# air_quality_monitor.net
KiCad netlist of a schematic drawn in Altium Designer
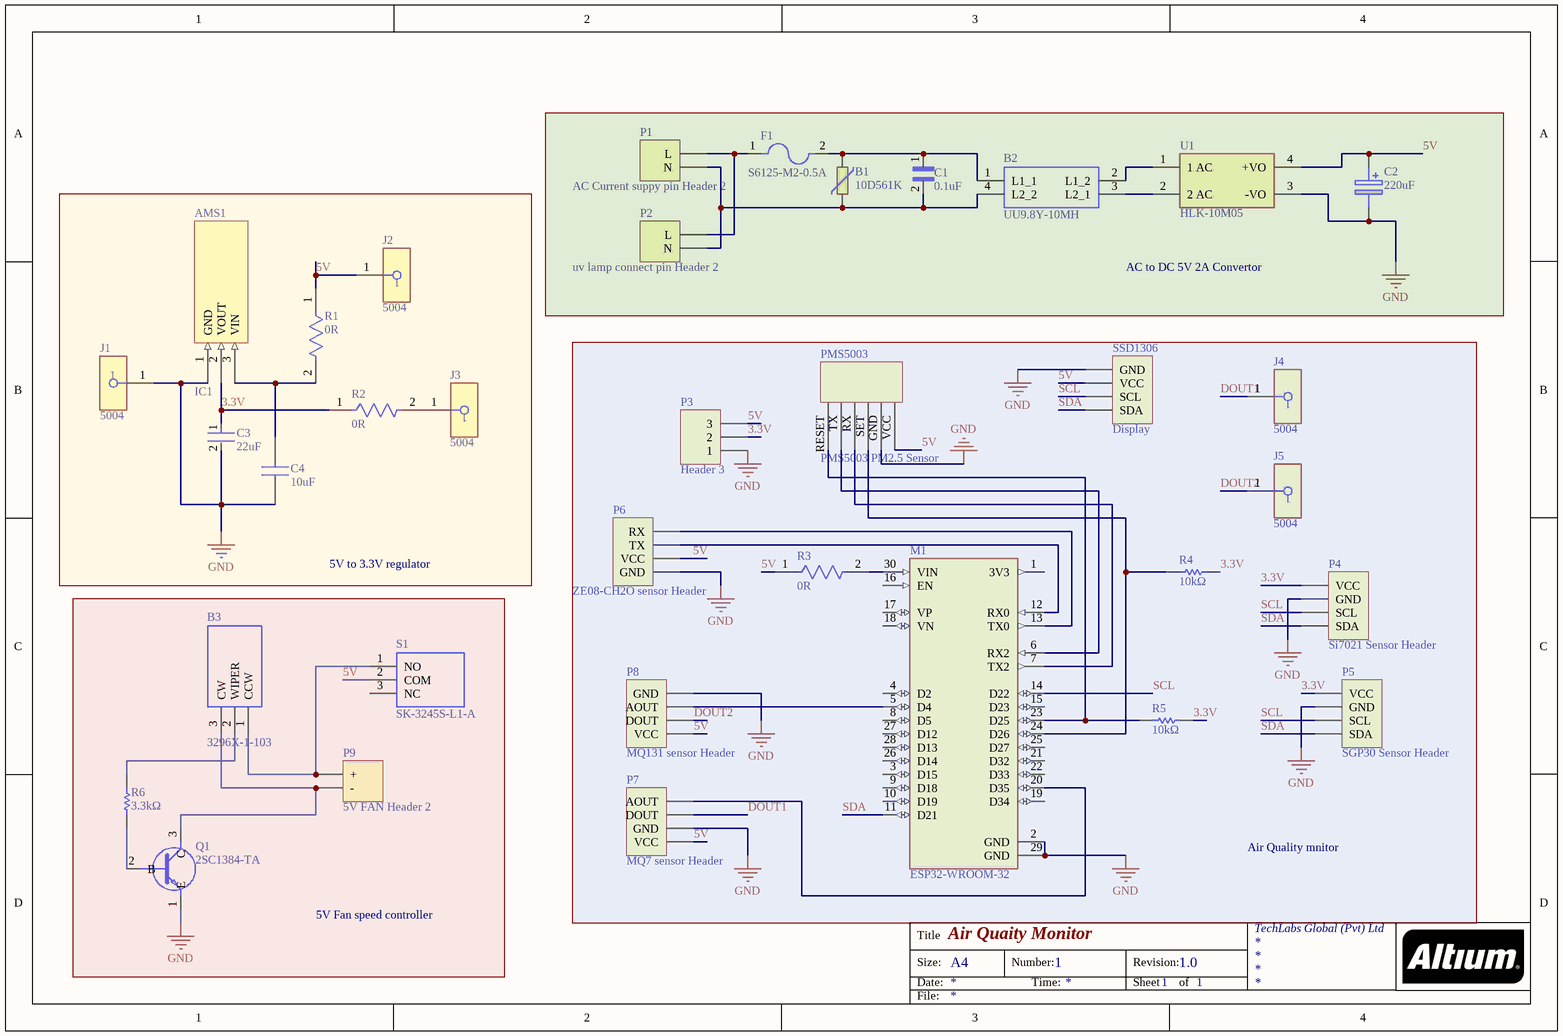
[diagram p0: air quality monitor.SchDoc]

(export (version "E")
  (design (tool "Eeschema 10.0.6"))
  (components
    (comp (ref "AMS1")
      (value "IC1")
      (footprint "SOT89-150P350X150-3N")
      (fields
        (field (name "MANUFACTURER") "YONGYUTAI")
        (field (name "MFR. PART #") "AMS1117-3.3")
        (field (name "LCSC PART #") "C2904742")
      )
      (libsource (lib "AMS1117-3.3") (part "IC?"))
    )
    (comp (ref "B1")
      (value "10D561K")
      (footprint "10D561K")
      (description "920V 42.3J 180pF@1kHz 460V 350V 504V~616V 2.5kA Plugin Varistors ROHS")
      (fields (field (name "LCSC PART #") "C113236") (field (name "MANUFACTURER") "Hongzhi Elec"))
      (libsource (lib "10D561K") (part "10D561K"))
    )
    (comp (ref "B2")
      (value "UU9.8Y-10MH")
      (footprint "UU98Y10MH")
      (description "10mH@1kHz 1.2Ω 2 500mA 50V Plugin Common Mode Filters ROHS")
      (fields
        (field (name "MANUFACTURER") "FH (Guangdong Fenghua Advanced Tech)")
        (field (name "LCSC PART#") "C75192")
      )
      (libsource (lib "UU9.8Y-10MH") (part "UU9.8Y-10MH"))
    )
    (comp (ref "B3")
      (value "3296X-1-103")
      (footprint "3296X1223LF")
      (description "±10% 10kΩ Plugin Variable Resistors/Potentiometers ROHS")
      (fields
        (field (name "MANUFACTURER") " BOCHEN(Chengdu Guosheng Tech)")
        (field (name "LCSC PART #") "C118955")
      )
      (libsource (lib "3296X-1-103") (part "3296X-1-103"))
    )
    (comp (ref "C1")
      (value "0.1uF")
      (footprint "MPX-104K275VAC-C-D2")
      (description "0.1uF ±10% -40℃~+110℃ X2 275VAC Radial Leaded,P=15mm Suppression Capacitors ROHS")
      (fields (field (name "LCSC PART #") "C3249976") (field (name "MANUFACTURER") "CORETONG"))
      (libsource (lib "MPX-104K275VAC-C-D2") (part "MPX-104K275VAC-C-D2"))
    )
    (comp (ref "C2")
      (value "220uF")
      (footprint "CAPAE830X1050N")
      (fields
        (field (name "MANUFACTURER") "Nichicon")
        (field (name "MFR.PART #") "UUR1C221MNL1GS")
        (field (name "LCSC PART#") "C445237")
      )
      (libsource (lib "UUR1C221MNL1GS") (part "UUR1C221MNL1GS"))
    )
    (comp (ref "C3")
      (value "22uF")
      (footprint "FP-GRM219-0_2-0_15-IPC_A")
      (description "Chip Multilayer Ceramic Capacitors for General Purpose, 0805, 22uF, X5R, 15%, 20%, 16V")
      (fields (field (name "MFR. PART #") "GRM219R61C226ME15L") (field (name "LCSC PART #") "C162295"))
      (libsource (lib "Altium Content Vault") (part "b4654b650e69147ec39a6b967a45e02"))
    )
    (comp (ref "C4")
      (value "10uF")
      (footprint "CAPC1005X70N")
      (description "6.3V 10uF X5R ±20% 0402 Multilayer Ceramic Capacitors MLCC - SMD/SMT ROHS")
      (fields
        (field (name "MANUFACTURER") "Samsung Electro-Mechanics")
        (field (name "MFR. PART #") "CL05A106MQ5NUNC")
      )
      (libsource (lib "CL05A106MQ5NUNC") (part "CL05A106MQ5NUNC"))
    )
    (comp (ref "F1")
      (value "S6125-M2-0.5A")
      (footprint "CAPC6125X25N")
      (description "SMD Fuses ROHS")
      (fields (field (name "LCSC PART #") "C845172") (field (name "MANUFACTURER") "SART(Nanjing Sart Tech)"))
      (libsource (lib "S6125-M2-0.5A") (part "S6125-M2-0.5A"))
    )
    (comp (ref "J1")
      (value "5004")
      (footprint "FP-5004-MFG")
      (description "PC TEST POINT MINIATURE YELLOW")
      (fields (field (name "MANUFACTURER") "Keystone") (field (name "LCSC PART #") "C2906762"))
      (libsource (lib "Altium Content Vault") (part "98815daf2f2c152b0c43f5ab9800df6"))
    )
    (comp (ref "J2")
      (value "5004")
      (footprint "FP-5004-MFG")
      (description "PC TEST POINT MINIATURE YELLOW")
      (fields (field (name "MANUFACTURER") "Keystone") (field (name "LCSC PART #") "C2906762"))
      (libsource (lib "") (part "98815daf2f2c152b0c43f5ab9800df6_1"))
    )
    (comp (ref "J3")
      (value "5004")
      (footprint "FP-5004-MFG")
      (description "PC TEST POINT MINIATURE YELLOW")
      (fields (field (name "MANUFACTURER") "Keystone") (field (name "LCSC PART #") "C2906762"))
      (libsource (lib "") (part "98815daf2f2c152b0c43f5ab9800df6_1"))
    )
    (comp (ref "J4")
      (value "5004")
      (footprint "FP-5004-MFG")
      (description "PC TEST POINT MINIATURE YELLOW")
      (fields (field (name "MANUFACTURER") "Keystone") (field (name "LCSC PART #") "C2906762"))
      (libsource (lib "") (part "98815daf2f2c152b0c43f5ab9800df6_1"))
    )
    (comp (ref "J5")
      (value "5004")
      (footprint "FP-5004-MFG")
      (description "PC TEST POINT MINIATURE YELLOW")
      (fields (field (name "MANUFACTURER") "Keystone") (field (name "LCSC PART #") "C2906762"))
      (libsource (lib "") (part "98815daf2f2c152b0c43f5ab9800df6_1"))
    )
    (comp (ref "M1")
      (value "ESP32-WROOM-32")
      (footprint "ESP32-DEVKIT-V1")
      (libsource (lib "Modules") (part "ESP32-DEVKIT-V1"))
    )
    (comp (ref "P1")
      (value "AC Current suppy pin Header 2")
      (footprint "HDR1X2")
      (description "Header, 2-Pin")
      (fields (field (name "PUBLISHER") "Altium Limited"))
      (libsource (lib "Miscellaneous Connectors") (part "Header 2"))
    )
    (comp (ref "P2")
      (value "uv lamp connect pin Header 2")
      (footprint "HDR1X2")
      (description "Header, 2-Pin")
      (fields (field (name "PUBLISHER") "Altium Limited"))
      (libsource (lib "Miscellaneous Connectors") (part "Header 2"))
    )
    (comp (ref "P3")
      (value "Header 3")
      (footprint "HDR1X3")
      (description "Header, 3-Pin")
      (fields (field (name "PUBLISHER") "Altium Limited"))
      (libsource (lib "Miscellaneous Connectors") (part "Header 3"))
    )
    (comp (ref "P4")
      (value "Si7021 Sensor Header")
      (footprint "HDR1X4")
      (description "Header, 4-Pin")
      (libsource (lib "Miscellaneous Connectors") (part "Header 4"))
    )
    (comp (ref "P5")
      (value "SGP30 Sensor Header")
      (footprint "HDR1X4")
      (description "Header, 4-Pin")
      (fields (field (name "PUBLISHER") "Altium Limited"))
      (libsource (lib "Miscellaneous Connectors") (part "Header 4"))
    )
    (comp (ref "P6")
      (value "ZE08-CH2O sensor Header")
      (footprint "HDR1X4")
      (description "- Sensor Modules ROHS")
      (fields
        (field (name "MFR.PART #") "ZE08-CH2O")
        (field (name "MANUFACTURER") "Zhengzhou Winsen Elec Tech")
      )
      (libsource (lib "") (part "Header 4_2"))
    )
    (comp (ref "P7")
      (value "MQ7 sensor Header")
      (footprint "HDR1X4")
      (description "Header, 4-Pin")
      (fields (field (name "PUBLISHER") "Altium Limited"))
      (libsource (lib "") (part "Header 4_1"))
    )
    (comp (ref "P8")
      (value "MQ131 sensor Header")
      (footprint "HDR1X4")
      (description "Header, 4-Pin")
      (fields (field (name "PUBLISHER") "Altium Limited"))
      (libsource (lib "") (part "Header 4_4"))
    )
    (comp (ref "P9")
      (value "5V FAN Header 2")
      (footprint "HDR1X2")
      (description "Header, 2-Pin")
      (fields (field (name "PUBLISHER") "Altium Limited"))
      (libsource (lib "") (part "Header 2_1"))
    )
    (comp (ref "PMS5003")
      (value "PMS5003 PM2.5 Sensor")
      (footprint "PMS5003 PM2.5 Sensor")
      (description "PMS5003 Sensor Modules ROHS")
      (fields (field (name "MFR.PART #") "PMS5003") (field (name "MANUFACTURER") "Beijing Plantower"))
      (libsource (lib "DIY Air Quality Monitor Library") (part "PMS5003 PM2.5 Sensor"))
    )
    (comp (ref "Q1")
      (value "2SC1384-TA")
      (footprint "2SC1384-TA")
      (description "TO-92-3 Bipolar Transistors - BJT ROHS")
      (fields
        (field (name "MANUFACTURER") "Jiangsu Changjing Electronics Technology Co., Ltd.")
        (field (name "LCSC PART #") "C2910422")
      )
      (libsource (lib "2SC1384-TA") (part "2SC1384-TA"))
    )
    (comp (ref "R1")
      (value "0R")
      (footprint "FP-RC0402-0_4-IPC_A")
      (description "RES SMD 0 OHM JUMPER 1/16W 0402")
      (fields (field (name "MANUFACTURER") "Yageo") (field (name "LCSC PART #") "C106231"))
      (libsource (lib "Altium Content Vault") (part "1029c3af85768c4190bb7ad29bc67b5"))
    )
    (comp (ref "R2")
      (value "0R")
      (footprint "FP-RC0402-0_4-IPC_A")
      (description "RES SMD 0 OHM JUMPER 1/16W 0402")
      (fields (field (name "MANUFACTURER") "Yageo") (field (name "LCSC PART #") "C106231"))
      (libsource (lib "Altium Content Vault") (part "1029c3af85768c4190bb7ad29bc67b5"))
    )
    (comp (ref "R3")
      (value "0R")
      (footprint "FP-RC0402-0_4-IPC_A")
      (description "RES SMD 0 OHM JUMPER 1/16W 0402")
      (fields (field (name "MANUFACTURER") "Yageo") (field (name "LCSC PART #") "C106231"))
      (libsource (lib "Altium Content Vault") (part "1029c3af85768c4190bb7ad29bc67b5"))
    )
    (comp (ref "R4")
      (value "10kΩ")
      (footprint "RESC1005X40X25LL05T10")
      (description "62.5mW 50V ±100ppm/℃ ±1% -55℃~+155℃ 10kΩ 0402 Chip Resistor - Surface Mount ROHS")
      (fields (field (name "MFR. PART #") "RC0402FR-0710KL") (field (name "MANUFACTURER") "Yageo / Phycomp"))
      (libsource (lib "Altium Content Vault") (part "RES"))
    )
    (comp (ref "R5")
      (value "10kΩ")
      (footprint "RESC1005X40X25LL05T10")
      (description "62.5mW 50V ±100ppm/℃ ±1% -55℃~+155℃ 10kΩ 0402 Chip Resistor - Surface Mount ROHS")
      (fields (field (name "MFR. PART #") "RC0402FR-0710KL") (field (name "MANUFACTURER") "Yageo / Phycomp"))
      (libsource (lib "Altium Content Vault") (part "RES"))
    )
    (comp (ref "R6")
      (value "3.3kΩ")
      (footprint "RESC1608X55X25ML10T15")
      (fields
        (field (name "MANUFACTURER") "YAGEO")
        (field (name "MFR. PART #") "RC0603FR-073K3L")
        (field (name "LCSC PART #") "C108078")
      )
      (libsource (lib "Altium Content Vault") (part "RES-2"))
    )
    (comp (ref "S1")
      (value "SK-3245S-L1-A")
      (footprint "SK3245SL1A")
      (fields (field (name "MANUFACTURER") "XKB Connectivity") (field (name "LCSC PART#") "C405951"))
      (libsource (lib "SK-3245S-L1-A") (part "SK-3245S-L1-A"))
    )
    (comp (ref "SSD1306")
      (value "Display")
      (footprint "HDR1X4")
      (description "Header, 4-Pin")
      (fields (field (name "PUBLISHER") "Altium Limited"))
      (libsource (lib "") (part "Header 4_3"))
    )
    (comp (ref "U1")
      (value "HLK-10M05")
      (footprint "FP-HLK-10M05-MFG")
      (description "5V 2A 90VAC~265VAC 1 120V~350V Isolated Regulated 10W AC-DC 80% Plugin Power Modules ROHS")
      (fields (field (name "MANUFACTURER") "HI-LINK") (field (name "LCSC PART#") "C403745"))
      (libsource (lib "Altium Content Vault") (part "a65b17ccb3a75dffb3c3e849074403b"))
    )
  )
  (nets
    (net (code "1") (name "/3.3V") (class "Default")
      (node (ref "AMS1") (pin "2") (pinfunction "VOUT_2") (pintype "input"))
      (node (ref "C3") (pin "1") (pinfunction "1_1") (pintype "passive"))
      (node (ref "P3") (pin "2") (pinfunction "2_2") (pintype "passive"))
      (node (ref "P4") (pin "1") (pinfunction "VCC_1") (pintype "passive"))
      (node (ref "P5") (pin "1") (pinfunction "VCC_1") (pintype "passive"))
      (node (ref "R2") (pin "1") (pinfunction "1_1") (pintype "passive"))
      (node (ref "R4") (pin "2") (pinfunction "2_2") (pintype "passive"))
      (node (ref "R5") (pin "2") (pinfunction "2_2") (pintype "passive"))
    )
    (net (code "2") (name "/5V") (class "Default")
      (node (ref "C2") (pin "1") (pinfunction "+_1") (pintype "passive"))
      (node (ref "J2") (pin "1") (pinfunction "1_1") (pintype "passive"))
      (node (ref "P3") (pin "3") (pinfunction "3_3") (pintype "passive"))
      (node (ref "P6") (pin "2") (pinfunction "VCC_2") (pintype "passive"))
      (node (ref "P7") (pin "1") (pinfunction "VCC_1") (pintype "passive"))
      (node (ref "P8") (pin "1") (pinfunction "VCC_1") (pintype "passive"))
      (node (ref "PMS5003") (pin "VCC") (pintype "passive"))
      (node (ref "R1") (pin "1") (pinfunction "1_1") (pintype "passive"))
      (node (ref "R3") (pin "1") (pinfunction "1_1") (pintype "passive"))
      (node (ref "S1") (pin "2") (pinfunction "COM_2") (pintype "passive"))
      (node (ref "SSD1306") (pin "2") (pinfunction "VCC_2") (pintype "passive"))
      (node (ref "U1") (pin "4") (pinfunction "+VO_4") (pintype "power_in"))
    )
    (net (code "3") (name "/DOUT1") (class "Default")
      (node (ref "J4") (pin "1") (pinfunction "1_1") (pintype "passive"))
      (node (ref "P7") (pin "3") (pinfunction "DOUT_3") (pintype "passive"))
    )
    (net (code "4") (name "/DOUT2") (class "Default")
      (node (ref "J5") (pin "1") (pinfunction "1_1") (pintype "passive"))
      (node (ref "P8") (pin "2") (pinfunction "DOUT_2") (pintype "passive"))
    )
    (net (code "5") (name "/SCL") (class "Default")
      (node (ref "M1") (pin "14") (pinfunction "D22_14") (pintype "bidirectional"))
      (node (ref "P4") (pin "3") (pinfunction "SCL_3") (pintype "passive"))
      (node (ref "P5") (pin "3") (pinfunction "SCL_3") (pintype "passive"))
      (node (ref "SSD1306") (pin "3") (pinfunction "SCL_3") (pintype "passive"))
    )
    (net (code "6") (name "/SDA") (class "Default")
      (node (ref "M1") (pin "11") (pinfunction "D21_11") (pintype "bidirectional"))
      (node (ref "P4") (pin "4") (pinfunction "SDA_4") (pintype "passive"))
      (node (ref "P5") (pin "4") (pinfunction "SDA_4") (pintype "passive"))
      (node (ref "SSD1306") (pin "4") (pinfunction "SDA_4") (pintype "passive"))
    )
    (net (code "7") (name "GND") (class "Default")
      (node (ref "AMS1") (pin "1") (pinfunction "GND_1") (pintype "input"))
      (node (ref "C2") (pin "2") (pinfunction "-_2") (pintype "passive"))
      (node (ref "C3") (pin "2") (pinfunction "2_2") (pintype "passive"))
      (node (ref "C4") (pin "1") (pinfunction "1_1") (pintype "passive"))
      (node (ref "J1") (pin "1") (pinfunction "1_1") (pintype "passive"))
      (node (ref "M1") (pin "2") (pinfunction "GND_2") (pintype "power_in"))
      (node (ref "M1") (pin "29") (pinfunction "GND_29") (pintype "power_in"))
      (node (ref "P3") (pin "1") (pinfunction "1_1") (pintype "passive"))
      (node (ref "P4") (pin "2") (pinfunction "GND_2") (pintype "passive"))
      (node (ref "P5") (pin "2") (pinfunction "GND_2") (pintype "passive"))
      (node (ref "P6") (pin "1") (pinfunction "GND_1") (pintype "passive"))
      (node (ref "P7") (pin "2") (pinfunction "GND_2") (pintype "passive"))
      (node (ref "P8") (pin "4") (pinfunction "GND_4") (pintype "passive"))
      (node (ref "PMS5003") (pin "GND") (pintype "passive"))
      (node (ref "Q1") (pin "1") (pinfunction "E_1") (pintype "passive"))
      (node (ref "SSD1306") (pin "1") (pinfunction "GND_1") (pintype "passive"))
      (node (ref "U1") (pin "3") (pinfunction "-VO_3") (pintype "power_in"))
    )
    (net (code "8") (name "Net-(AMS1-VIN)") (class "Default")
      (node (ref "AMS1") (pin "3") (pinfunction "VIN_3") (pintype "input"))
      (node (ref "C4") (pin "2") (pinfunction "2_2") (pintype "passive"))
      (node (ref "R1") (pin "2") (pinfunction "2_2") (pintype "passive"))
    )
    (net (code "9") (name "Net-(B2-L1_1)") (class "Default")
      (node (ref "B1") (pin "1") (pinfunction "1_1") (pintype "passive"))
      (node (ref "B2") (pin "1") (pinfunction "L1_1_1") (pintype "passive"))
      (node (ref "C1") (pin "1") (pinfunction "1_1") (pintype "passive"))
      (node (ref "F1") (pin "2") (pinfunction "2_2") (pintype "passive"))
    )
    (net (code "10") (name "Net-(B2-L1_2)") (class "Default")
      (node (ref "B2") (pin "2") (pinfunction "L1_2_2") (pintype "passive"))
      (node (ref "U1") (pin "1") (pinfunction "1_AC_1") (pintype "passive"))
    )
    (net (code "11") (name "Net-(B2-L2_1)") (class "Default")
      (node (ref "B2") (pin "3") (pinfunction "L2_1_3") (pintype "passive"))
      (node (ref "U1") (pin "2") (pinfunction "2_AC_2") (pintype "passive"))
    )
    (net (code "12") (name "Net-(B2-L2_2)") (class "Default")
      (node (ref "B1") (pin "2") (pinfunction "2_2") (pintype "passive"))
      (node (ref "B2") (pin "4") (pinfunction "L2_2_4") (pintype "passive"))
      (node (ref "C1") (pin "2") (pinfunction "2_2") (pintype "passive"))
      (node (ref "P1") (pin "1") (pinfunction "N_1") (pintype "passive"))
      (node (ref "P2") (pin "1") (pinfunction "N_1") (pintype "passive"))
    )
    (net (code "13") (name "Net-(B3-CCW)") (class "Default")
      (node (ref "B3") (pin "1") (pinfunction "CCW_1") (pintype "passive"))
      (node (ref "P9") (pin "1") (pinfunction "+_1") (pintype "passive"))
      (node (ref "S1") (pin "1") (pinfunction "NO_1") (pintype "passive"))
    )
    (net (code "14") (name "Net-(B3-CW)") (class "Default")
      (node (ref "B3") (pin "3") (pinfunction "CW_3") (pintype "passive"))
      (node (ref "P9") (pin "2") (pinfunction "-_2") (pintype "passive"))
      (node (ref "Q1") (pin "3") (pinfunction "C_3") (pintype "passive"))
    )
    (net (code "15") (name "Net-(B3-WIPER)") (class "Default")
      (node (ref "B3") (pin "2") (pinfunction "WIPER_2") (pintype "passive"))
      (node (ref "R6") (pin "2") (pinfunction "2_2") (pintype "passive"))
    )
    (net (code "16") (name "Net-(J3-Pad1)") (class "Default")
      (node (ref "J3") (pin "1") (pinfunction "1_1") (pintype "passive"))
      (node (ref "R2") (pin "2") (pinfunction "2_2") (pintype "passive"))
    )
    (net (code "17") (name "Net-(M1-D4)") (class "Default")
      (node (ref "M1") (pin "5") (pinfunction "D4_5") (pintype "bidirectional"))
      (node (ref "P8") (pin "3") (pinfunction "AOUT_3") (pintype "passive"))
    )
    (net (code "18") (name "Net-(M1-D25)") (class "Default")
      (node (ref "M1") (pin "23") (pinfunction "D25_23") (pintype "bidirectional"))
      (node (ref "PMS5003") (pin "RESET") (pintype "passive"))
      (node (ref "R5") (pin "1") (pinfunction "1_1") (pintype "passive"))
    )
    (net (code "19") (name "Net-(M1-D26)") (class "Default")
      (node (ref "M1") (pin "24") (pinfunction "D26_24") (pintype "bidirectional"))
      (node (ref "PMS5003") (pin "SET") (pintype "passive"))
      (node (ref "R4") (pin "1") (pinfunction "1_1") (pintype "passive"))
    )
    (net (code "20") (name "Net-(M1-D35)") (class "Default")
      (node (ref "M1") (pin "20") (pinfunction "D35_20") (pintype "bidirectional"))
      (node (ref "P7") (pin "4") (pinfunction "AOUT_4") (pintype "passive"))
    )
    (net (code "21") (name "Net-(M1-RX0)") (class "Default")
      (node (ref "M1") (pin "12") (pinfunction "RX0_12") (pintype "input"))
      (node (ref "P6") (pin "3") (pinfunction "TX_3") (pintype "passive"))
    )
    (net (code "22") (name "Net-(M1-RX2)") (class "Default")
      (node (ref "M1") (pin "6") (pinfunction "RX2_6") (pintype "input"))
      (node (ref "PMS5003") (pin "TX") (pintype "passive"))
    )
    (net (code "23") (name "Net-(M1-TX0)") (class "Default")
      (node (ref "M1") (pin "13") (pinfunction "TX0_13") (pintype "output"))
      (node (ref "P6") (pin "4") (pinfunction "RX_4") (pintype "passive"))
    )
    (net (code "24") (name "Net-(M1-TX2)") (class "Default")
      (node (ref "M1") (pin "7") (pinfunction "TX2_7") (pintype "output"))
      (node (ref "PMS5003") (pin "RX") (pintype "passive"))
    )
    (net (code "25") (name "Net-(M1-VIN)") (class "Default")
      (node (ref "M1") (pin "30") (pinfunction "VIN_30") (pintype "input"))
      (node (ref "R3") (pin "2") (pinfunction "2_2") (pintype "passive"))
    )
    (net (code "26") (name "Net-(P1-L)") (class "Default")
      (node (ref "F1") (pin "1") (pinfunction "1_1") (pintype "passive"))
      (node (ref "P1") (pin "2") (pinfunction "L_2") (pintype "passive"))
      (node (ref "P2") (pin "2") (pinfunction "L_2") (pintype "passive"))
    )
    (net (code "27") (name "Net-(Q1-B)") (class "Default")
      (node (ref "Q1") (pin "2") (pinfunction "B_2") (pintype "passive"))
      (node (ref "R6") (pin "1") (pinfunction "1_1") (pintype "passive"))
    )
    (net (code "28") (name "unconnected-(M1-3V3-Pad1)") (class "Default")
      (node (ref "M1") (pin "1") (pinfunction "3V3_1") (pintype "output"))
    )
    (net (code "29") (name "unconnected-(M1-D2-Pad4)") (class "Default")
      (node (ref "M1") (pin "4") (pinfunction "D2_4") (pintype "bidirectional"))
    )
    (net (code "30") (name "unconnected-(M1-D5-Pad8)") (class "Default")
      (node (ref "M1") (pin "8") (pinfunction "D5_8") (pintype "bidirectional"))
    )
    (net (code "31") (name "unconnected-(M1-D12-Pad27)") (class "Default")
      (node (ref "M1") (pin "27") (pinfunction "D12_27") (pintype "bidirectional"))
    )
    (net (code "32") (name "unconnected-(M1-D13-Pad28)") (class "Default")
      (node (ref "M1") (pin "28") (pinfunction "D13_28") (pintype "bidirectional"))
    )
    (net (code "33") (name "unconnected-(M1-D14-Pad26)") (class "Default")
      (node (ref "M1") (pin "26") (pinfunction "D14_26") (pintype "bidirectional"))
    )
    (net (code "34") (name "unconnected-(M1-D15-Pad3)") (class "Default")
      (node (ref "M1") (pin "3") (pinfunction "D15_3") (pintype "bidirectional"))
    )
    (net (code "35") (name "unconnected-(M1-D18-Pad9)") (class "Default")
      (node (ref "M1") (pin "9") (pinfunction "D18_9") (pintype "bidirectional"))
    )
    (net (code "36") (name "unconnected-(M1-D19-Pad10)") (class "Default")
      (node (ref "M1") (pin "10") (pinfunction "D19_10") (pintype "bidirectional"))
    )
    (net (code "37") (name "unconnected-(M1-D23-Pad15)") (class "Default")
      (node (ref "M1") (pin "15") (pinfunction "D23_15") (pintype "bidirectional"))
    )
    (net (code "38") (name "unconnected-(M1-D27-Pad25)") (class "Default")
      (node (ref "M1") (pin "25") (pinfunction "D27_25") (pintype "bidirectional"))
    )
    (net (code "39") (name "unconnected-(M1-D32-Pad21)") (class "Default")
      (node (ref "M1") (pin "21") (pinfunction "D32_21") (pintype "bidirectional"))
    )
    (net (code "40") (name "unconnected-(M1-D33-Pad22)") (class "Default")
      (node (ref "M1") (pin "22") (pinfunction "D33_22") (pintype "bidirectional"))
    )
    (net (code "41") (name "unconnected-(M1-D34-Pad19)") (class "Default")
      (node (ref "M1") (pin "19") (pinfunction "D34_19") (pintype "bidirectional"))
    )
    (net (code "42") (name "unconnected-(M1-EN-Pad16)") (class "Default")
      (node (ref "M1") (pin "16") (pinfunction "EN_16") (pintype "input"))
    )
    (net (code "43") (name "unconnected-(M1-VN-Pad18)") (class "Default")
      (node (ref "M1") (pin "18") (pinfunction "VN_18") (pintype "bidirectional"))
    )
    (net (code "44") (name "unconnected-(M1-VP-Pad17)") (class "Default")
      (node (ref "M1") (pin "17") (pinfunction "VP_17") (pintype "bidirectional"))
    )
    (net (code "45") (name "unconnected-(S1-NC-Pad3)") (class "Default")
      (node (ref "S1") (pin "3") (pinfunction "NC_3") (pintype "passive"))
    )
  )
)
